# DAQ.net
KiCad netlist of a schematic drawn in Altium Designer
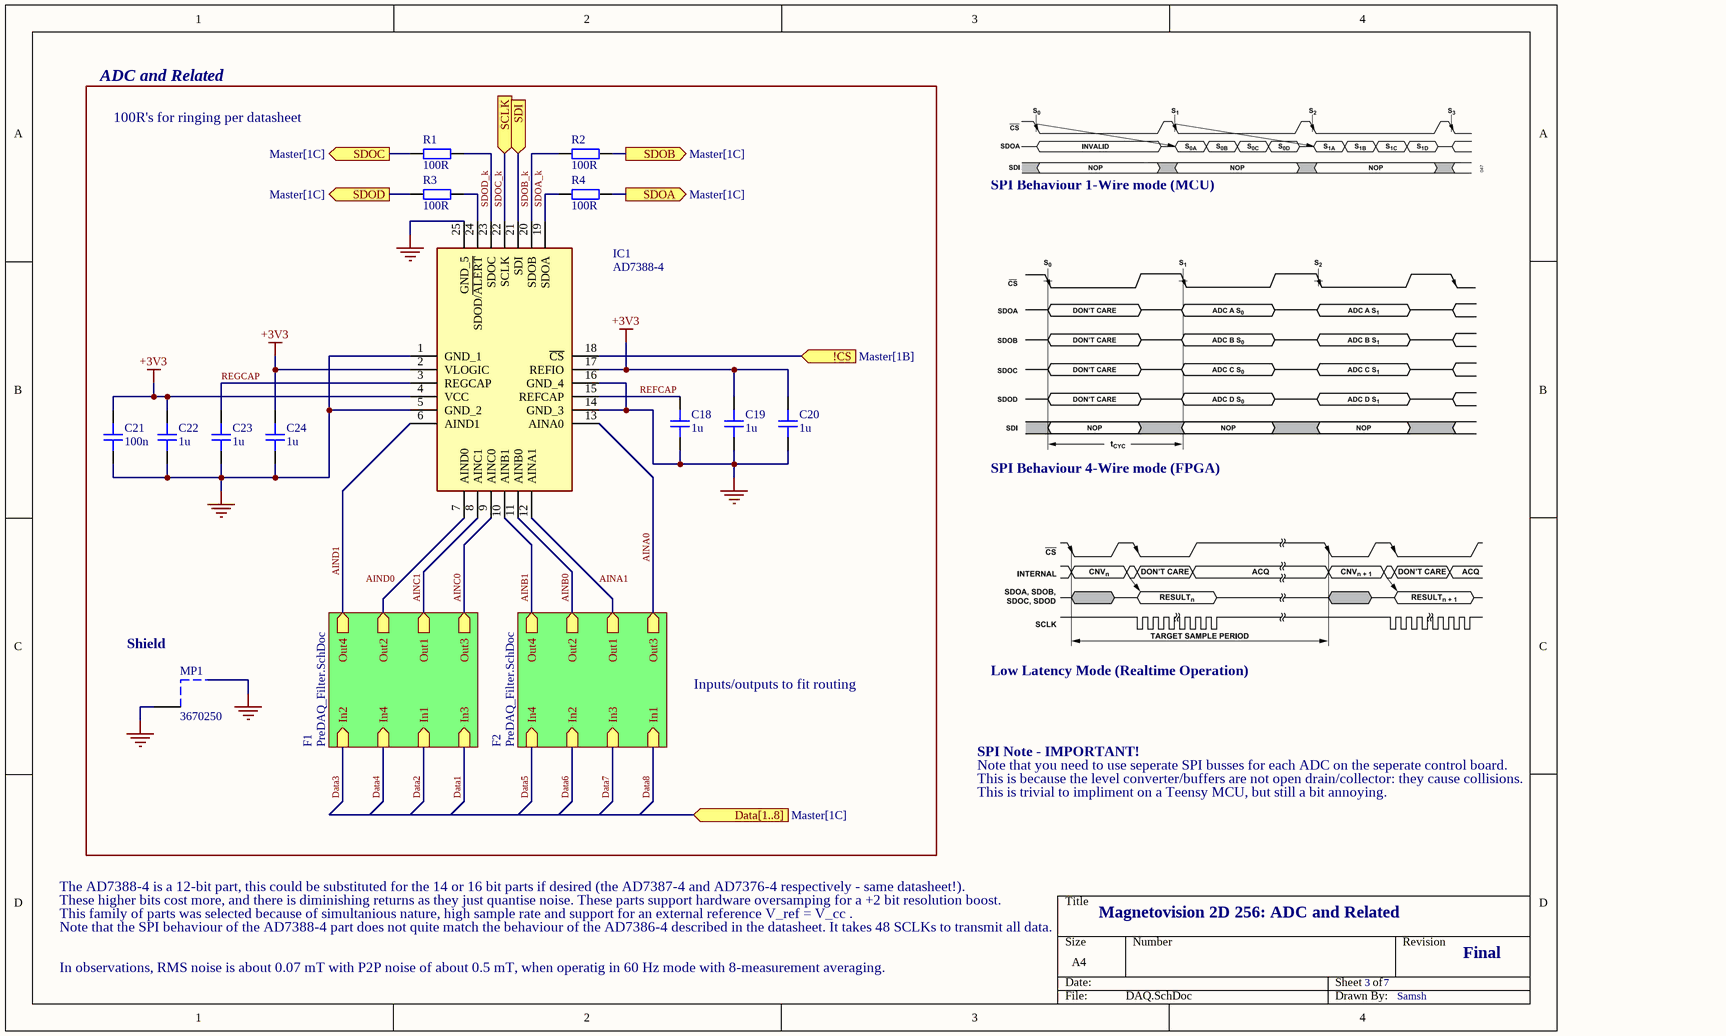
[diagram p0: DAQ.SchDoc]

(export (version "E")
  (design (tool "Eeschema 10.0.6"))
  (components
    (comp (ref "C18")
      (value "1u")
      (footprint "CAP_0603")
      (description "Capacitor SMD 0603")
      (fields (field (name "SOURCE") "Schematic-Lib-PhilsLab.SchLib"))
      (libsource (lib "Samsh Nanoelectronics") (part "CAP_EL_NP_5MM"))
    )
    (comp (ref "C19")
      (value "1u")
      (footprint "CAP_0603")
      (description "Capacitor SMD 0603")
      (fields (field (name "SOURCE") "Schematic-Lib-PhilsLab.SchLib"))
      (libsource (lib "Samsh Nanoelectronics") (part "CAP_EL_NP_5MM"))
    )
    (comp (ref "C20")
      (value "1u")
      (footprint "CAP_0603")
      (description "Capacitor SMD 0603")
      (fields (field (name "SOURCE") "Schematic-Lib-PhilsLab.SchLib"))
      (libsource (lib "Samsh Nanoelectronics") (part "CAP_EL_NP_5MM"))
    )
    (comp (ref "C21")
      (value "100n")
      (footprint "CAP_0603")
      (description "Capacitor SMD 0603")
      (fields (field (name "SOURCE") "Schematic-Lib-PhilsLab.SchLib"))
      (libsource (lib "Samsh Nanoelectronics") (part "CAP_EL_NP_5MM"))
    )
    (comp (ref "C22")
      (value "1u")
      (footprint "CAP_0603")
      (description "Capacitor SMD 0603")
      (fields (field (name "SOURCE") "Schematic-Lib-PhilsLab.SchLib"))
      (libsource (lib "Samsh Nanoelectronics") (part "CAP_EL_NP_5MM"))
    )
    (comp (ref "C23")
      (value "1u")
      (footprint "CAP_0603")
      (description "Capacitor SMD 0603")
      (fields (field (name "SOURCE") "Schematic-Lib-PhilsLab.SchLib"))
      (libsource (lib "Samsh Nanoelectronics") (part "CAP_EL_NP_5MM"))
    )
    (comp (ref "C24")
      (value "1u")
      (footprint "CAP_0603")
      (description "Capacitor SMD 0603")
      (fields (field (name "SOURCE") "Schematic-Lib-PhilsLab.SchLib"))
      (libsource (lib "Samsh Nanoelectronics") (part "CAP_EL_NP_5MM"))
    )
    (comp (ref "IC1")
      (value "AD7388-4")
      (footprint "QFN50P400X400X60-25N-D")
      (description "Single-Ended Input, Quad, Simultaneous Sampling, 16-Bit, SAR ADC")
      (fields
        (field (name "MANUFACTURER_PART_NUMBER") "AD7386-4BCPZ")
        (field (name "ARROW PART NUMBER") "AD7386-4")
      )
      (libsource (lib "Samsh Nanoelectronics") (part "AD7386-4BCPZ"))
    )
    (comp (ref "MP1")
      (value "3670250")
      (footprint "3670250")
      (description "3670250 Shield Cabinet Frame, 25Mm X 21Mm Rohs Compliant: Yes")
      (libsource (lib "Altium Content Vault") (part "WE-SHC"))
    )
    (comp (ref "R1")
      (value "100R")
      (footprint "RES_0603")
      (description "Resistor SMD 0603")
      (fields (field (name "SOURCE") "Schematic-Lib-PhilsLab.SchLib"))
      (libsource (lib "Samsh Nanoelectronics") (part "RES_5931"))
    )
    (comp (ref "R2")
      (value "100R")
      (footprint "RES_0603")
      (description "Resistor SMD 0603")
      (fields (field (name "SOURCE") "Schematic-Lib-PhilsLab.SchLib"))
      (libsource (lib "Samsh Nanoelectronics") (part "RES_5931"))
    )
    (comp (ref "R3")
      (value "100R")
      (footprint "RES_0603")
      (description "Resistor SMD 0603")
      (fields (field (name "SOURCE") "Schematic-Lib-PhilsLab.SchLib"))
      (libsource (lib "Samsh Nanoelectronics") (part "RES_5931"))
    )
    (comp (ref "R4")
      (value "100R")
      (footprint "RES_0603")
      (description "Resistor SMD 0603")
      (fields (field (name "SOURCE") "Schematic-Lib-PhilsLab.SchLib"))
      (libsource (lib "Samsh Nanoelectronics") (part "RES_5931"))
    )
  )
  (nets
    (net (code "1") (name "+3V3") (class "Default")
      (node (ref "C19") (pin "2") (pinfunction "2_2") (pintype "passive"))
      (node (ref "C20") (pin "2") (pinfunction "2_2") (pintype "passive"))
      (node (ref "C21") (pin "2") (pinfunction "2_2") (pintype "passive"))
      (node (ref "C22") (pin "2") (pinfunction "2_2") (pintype "passive"))
      (node (ref "C24") (pin "2") (pinfunction "2_2") (pintype "passive"))
      (node (ref "IC1") (pin "17") (pinfunction "REFIO_17") (pintype "passive"))
      (node (ref "IC1") (pin "2") (pinfunction "VLOGIC_2") (pintype "passive"))
      (node (ref "IC1") (pin "4") (pinfunction "VCC_4") (pintype "passive"))
    )
    (net (code "2") (name "/!CS") (class "Default")
      (node (ref "IC1") (pin "18") (pinfunction "~{CS}_18") (pintype "passive"))
    )
    (net (code "3") (name "/AINA0") (class "Default")
      (node (ref "IC1") (pin "13") (pinfunction "AINA0_13") (pintype "passive"))
    )
    (net (code "4") (name "/AINA1") (class "Default")
      (node (ref "IC1") (pin "12") (pinfunction "AINA1_12") (pintype "passive"))
    )
    (net (code "5") (name "/AINB0") (class "Default")
      (node (ref "IC1") (pin "11") (pinfunction "AINB0_11") (pintype "passive"))
    )
    (net (code "6") (name "/AINB1") (class "Default")
      (node (ref "IC1") (pin "10") (pinfunction "AINB1_10") (pintype "passive"))
    )
    (net (code "7") (name "/AINC0") (class "Default")
      (node (ref "IC1") (pin "9") (pinfunction "AINC0_9") (pintype "passive"))
    )
    (net (code "8") (name "/AINC1") (class "Default")
      (node (ref "IC1") (pin "8") (pinfunction "AINC1_8") (pintype "passive"))
    )
    (net (code "9") (name "/AIND0") (class "Default")
      (node (ref "IC1") (pin "7") (pinfunction "AIND0_7") (pintype "passive"))
    )
    (net (code "10") (name "/AIND1") (class "Default")
      (node (ref "IC1") (pin "6") (pinfunction "AIND1_6") (pintype "passive"))
    )
    (net (code "20") (name "/REFCAP") (class "Default")
      (node (ref "C18") (pin "2") (pinfunction "2_2") (pintype "passive"))
      (node (ref "IC1") (pin "15") (pinfunction "REFCAP_15") (pintype "passive"))
    )
    (net (code "21") (name "/REGCAP") (class "Default")
      (node (ref "C23") (pin "2") (pinfunction "2_2") (pintype "passive"))
      (node (ref "IC1") (pin "3") (pinfunction "REGCAP_3") (pintype "passive"))
    )
    (net (code "22") (name "/SCLK") (class "Default")
      (node (ref "IC1") (pin "22") (pinfunction "SCLK_22") (pintype "passive"))
    )
    (net (code "23") (name "/SDI") (class "Default")
      (node (ref "IC1") (pin "21") (pinfunction "SDI_21") (pintype "passive"))
    )
    (net (code "24") (name "/SDOA") (class "Default")
      (node (ref "R4") (pin "1") (pinfunction "1_1") (pintype "passive"))
    )
    (net (code "25") (name "/SDOA_k") (class "Default")
      (node (ref "IC1") (pin "19") (pinfunction "SDOA_19") (pintype "passive"))
      (node (ref "R4") (pin "2") (pinfunction "2_2") (pintype "passive"))
    )
    (net (code "26") (name "/SDOB") (class "Default")
      (node (ref "R2") (pin "1") (pinfunction "1_1") (pintype "passive"))
    )
    (net (code "27") (name "/SDOB_k") (class "Default")
      (node (ref "IC1") (pin "20") (pinfunction "SDOB_20") (pintype "passive"))
      (node (ref "R2") (pin "2") (pinfunction "2_2") (pintype "passive"))
    )
    (net (code "28") (name "/SDOC") (class "Default")
      (node (ref "R1") (pin "2") (pinfunction "2_2") (pintype "passive"))
    )
    (net (code "29") (name "/SDOC_k") (class "Default")
      (node (ref "IC1") (pin "23") (pinfunction "SDOC_23") (pintype "passive"))
      (node (ref "R1") (pin "1") (pinfunction "1_1") (pintype "passive"))
    )
    (net (code "30") (name "/SDOD") (class "Default")
      (node (ref "R3") (pin "2") (pinfunction "2_2") (pintype "passive"))
    )
    (net (code "31") (name "/SDOD_k") (class "Default")
      (node (ref "IC1") (pin "24") (pinfunction "SDOD/~{ALERT}_24") (pintype "passive"))
      (node (ref "R3") (pin "1") (pinfunction "1_1") (pintype "passive"))
    )
    (net (code "32") (name "GND") (class "Default")
      (node (ref "C18") (pin "1") (pinfunction "1_1") (pintype "passive"))
      (node (ref "C19") (pin "1") (pinfunction "1_1") (pintype "passive"))
      (node (ref "C20") (pin "1") (pinfunction "1_1") (pintype "passive"))
      (node (ref "C21") (pin "1") (pinfunction "1_1") (pintype "passive"))
      (node (ref "C22") (pin "1") (pinfunction "1_1") (pintype "passive"))
      (node (ref "C23") (pin "1") (pinfunction "1_1") (pintype "passive"))
      (node (ref "C24") (pin "1") (pinfunction "1_1") (pintype "passive"))
      (node (ref "IC1") (pin "1") (pinfunction "GND_1_1") (pintype "passive"))
      (node (ref "IC1") (pin "14") (pinfunction "GND_3_14") (pintype "passive"))
      (node (ref "IC1") (pin "16") (pinfunction "GND_4_16") (pintype "passive"))
      (node (ref "IC1") (pin "25") (pinfunction "GND_5_25") (pintype "passive"))
      (node (ref "IC1") (pin "5") (pinfunction "GND_2_5") (pintype "passive"))
      (node (ref "MP1") (pin "1") (pinfunction "1_1") (pintype "passive"))
    )
  )
)
